# sht31.net
KiCad netlist of a schematic drawn in EAGLE
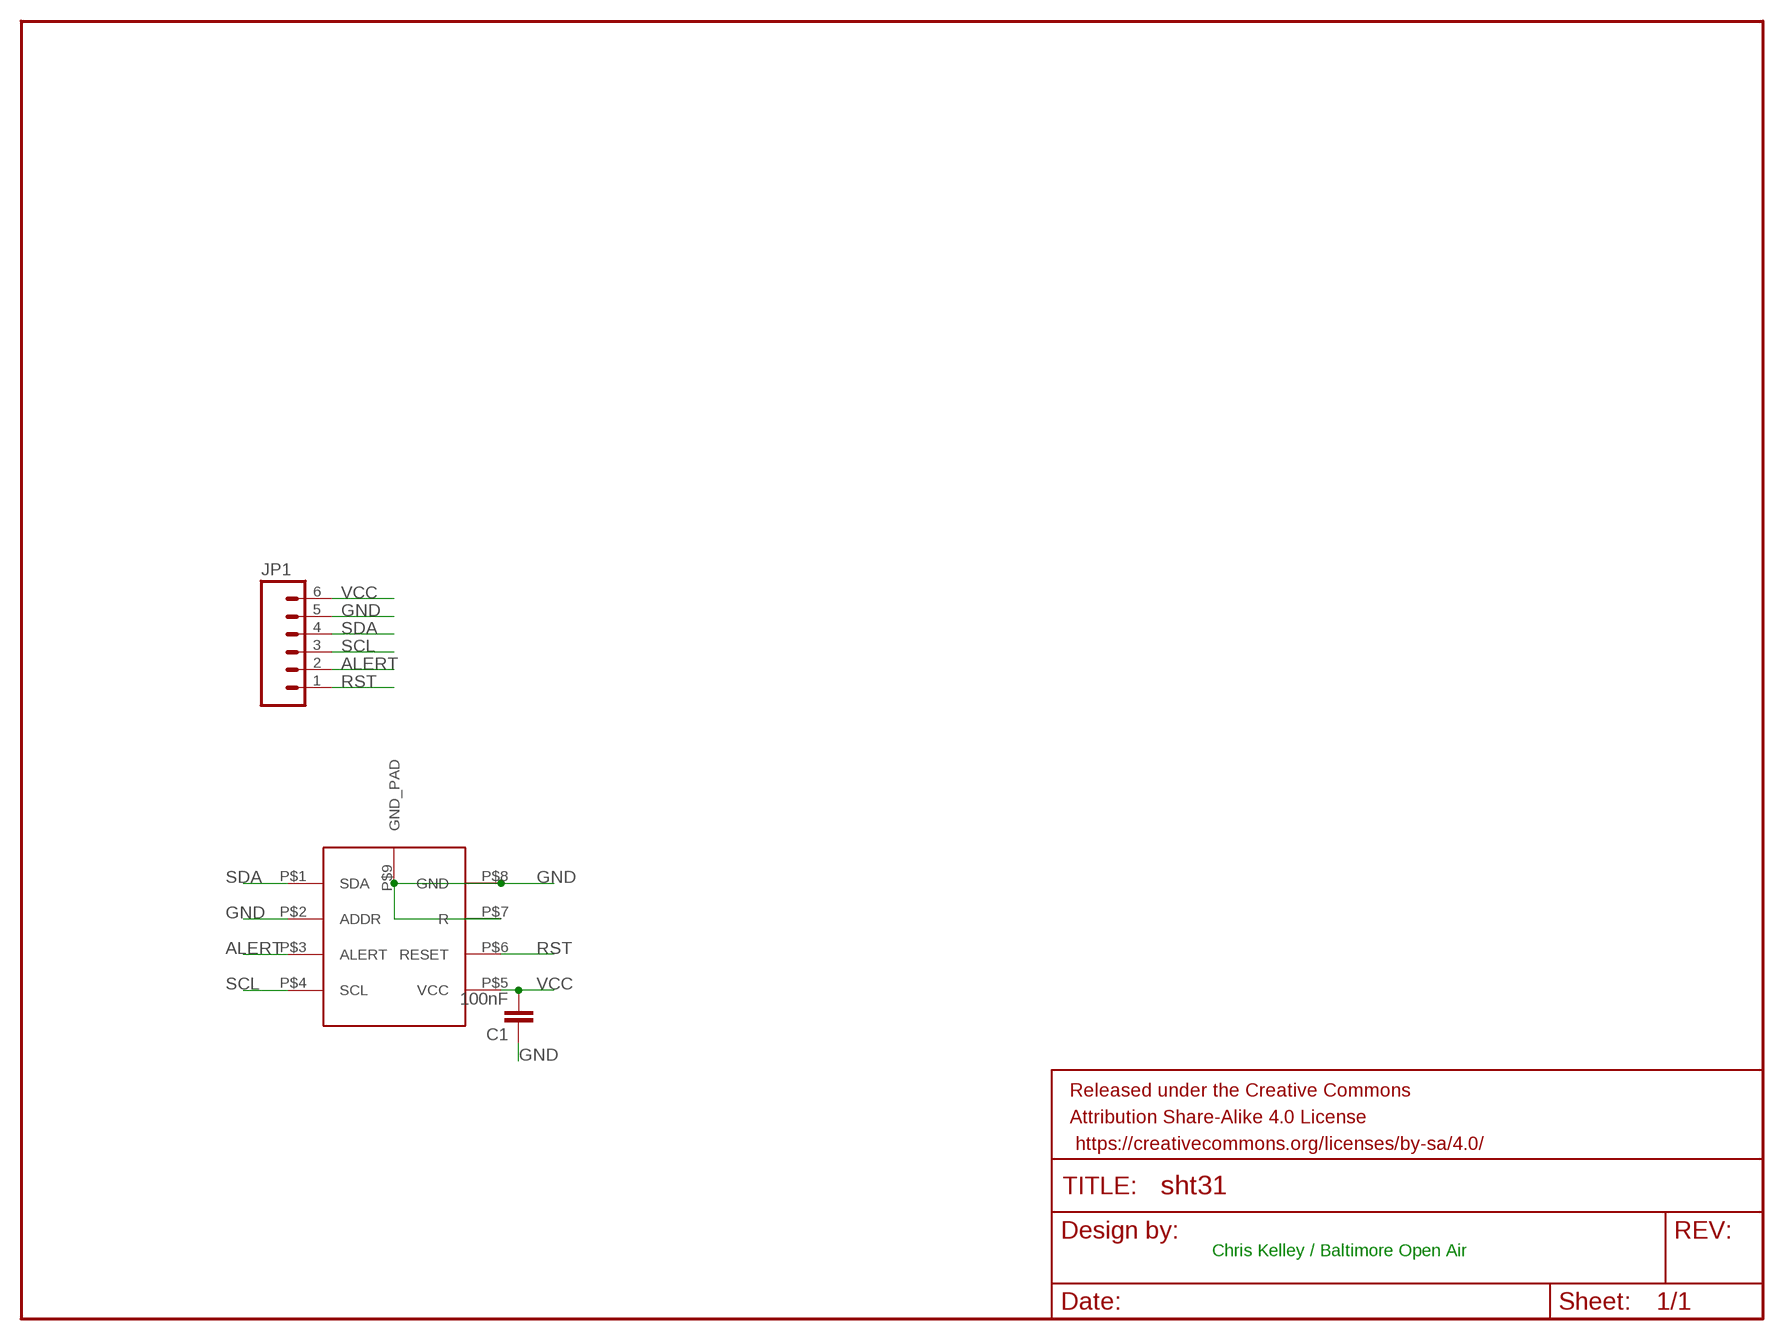
[diagram p0: schematic, sheet 1]

(export (version "E")
  (design (tool "Eeschema 10.0.6"))
  (components
    (comp (ref "C1")
      (value "100nF")
      (footprint "eagle-import:0603-CAP")
      (libsource (lib "eagle-import") (part "CAP0603-CAP"))
    )
    (comp (ref "FRAME1")
      (value "FRAME-LETTER")
      (footprint "eagle-import:CREATIVE_COMMONS")
      (libsource (lib "eagle-import") (part "FRAME-LETTER"))
    )
    (comp (ref "JP1")
      (value "M06SILK_FEMALE_PTH")
      (footprint "eagle-import:1X06")
      (libsource (lib "eagle-import") (part "M06SILK_FEMALE_PTH"))
    )
    (comp (ref "U$1")
      (value "SHT31-D")
      (footprint "eagle-import:SHT31-D")
      (libsource (lib "eagle-import") (part "SHT31-D"))
    )
  )
  (nets
    (net (code "1") (name "/ALERT") (class "Default")
      (node (ref "JP1") (pin "2") (pinfunction "2_2") (pintype "passive"))
      (node (ref "U$1") (pin "P$3") (pinfunction "ALERT_P$3") (pintype "bidirectional"))
    )
    (net (code "2") (name "/GND") (class "Default")
      (node (ref "C1") (pin "1") (pinfunction "1_1") (pintype "passive"))
      (node (ref "JP1") (pin "5") (pinfunction "5_5") (pintype "passive"))
      (node (ref "U$1") (pin "P$2") (pinfunction "ADDR_P$2") (pintype "bidirectional"))
      (node (ref "U$1") (pin "P$7") (pinfunction "R_P$7") (pintype "bidirectional"))
      (node (ref "U$1") (pin "P$8") (pinfunction "GND_P$8") (pintype "bidirectional"))
      (node (ref "U$1") (pin "P$9") (pinfunction "GND_PAD_P$9") (pintype "bidirectional"))
    )
    (net (code "3") (name "/RST") (class "Default")
      (node (ref "JP1") (pin "1") (pinfunction "1_1") (pintype "passive"))
      (node (ref "U$1") (pin "P$6") (pinfunction "RESET_P$6") (pintype "bidirectional"))
    )
    (net (code "4") (name "/SCL") (class "Default")
      (node (ref "JP1") (pin "3") (pinfunction "3_3") (pintype "passive"))
      (node (ref "U$1") (pin "P$4") (pinfunction "SCL_P$4") (pintype "bidirectional"))
    )
    (net (code "5") (name "/SDA") (class "Default")
      (node (ref "JP1") (pin "4") (pinfunction "4_4") (pintype "passive"))
      (node (ref "U$1") (pin "P$1") (pinfunction "SDA_P$1") (pintype "bidirectional"))
    )
    (net (code "6") (name "/VCC") (class "Default")
      (node (ref "C1") (pin "2") (pinfunction "2_2") (pintype "passive"))
      (node (ref "JP1") (pin "6") (pinfunction "6_6") (pintype "passive"))
      (node (ref "U$1") (pin "P$5") (pinfunction "VCC_P$5") (pintype "bidirectional"))
    )
  )
)
